# LEDs.net
KiCad netlist of a schematic drawn in Altium Designer
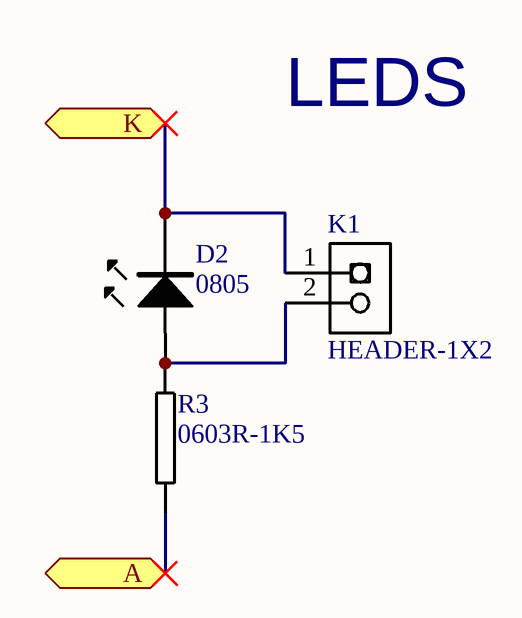
[diagram p0: LEDs.SchDoc]

(export (version "E")
  (design (tool "Eeschema 10.0.6"))
  (components
    (comp (ref "D2")
      (value "0805")
      (footprint "0805LED")
      (libsource (lib "RVA_LED_SMD_0805") (part "0805_LED"))
    )
    (comp (ref "K1")
      (value "HEADER-1X2")
      (footprint "HEADER-1X2")
      (libsource (lib "RVA_Altium_Library") (part "HEADER-1X2"))
    )
    (comp (ref "R3")
      (value "0603R-1K5")
      (footprint "0603R-1k5")
      (description "GENERIC RESISTOR 0603")
      (fields (field (name "MANUFACTURER PART NUMBER") "RMCF 1/16 15K 1% R") (field (name "TOLERANCE") "±1%"))
      (libsource (lib "RVA_Altium_Library") (part "0603R-1K5"))
    )
  )
  (nets
    (net (code "1") (name "/A") (class "Default") (node (ref "R3") (pin "2") (pintype "passive+no_connect")))
    (net (code "2") (name "/K") (class "Default")
      (node (ref "D2") (pin "K") (pintype "passive"))
      (node (ref "K1") (pin "1") (pintype "passive"))
    )
    (net (code "3") (name "Net-(D2-PadA)") (class "Default")
      (node (ref "D2") (pin "A") (pintype "passive"))
      (node (ref "K1") (pin "2") (pintype "passive"))
      (node (ref "R3") (pin "1") (pintype "passive"))
    )
  )
)
